# SCH_ECE198-10.net
KiCad netlist of a schematic drawn in EasyEDA
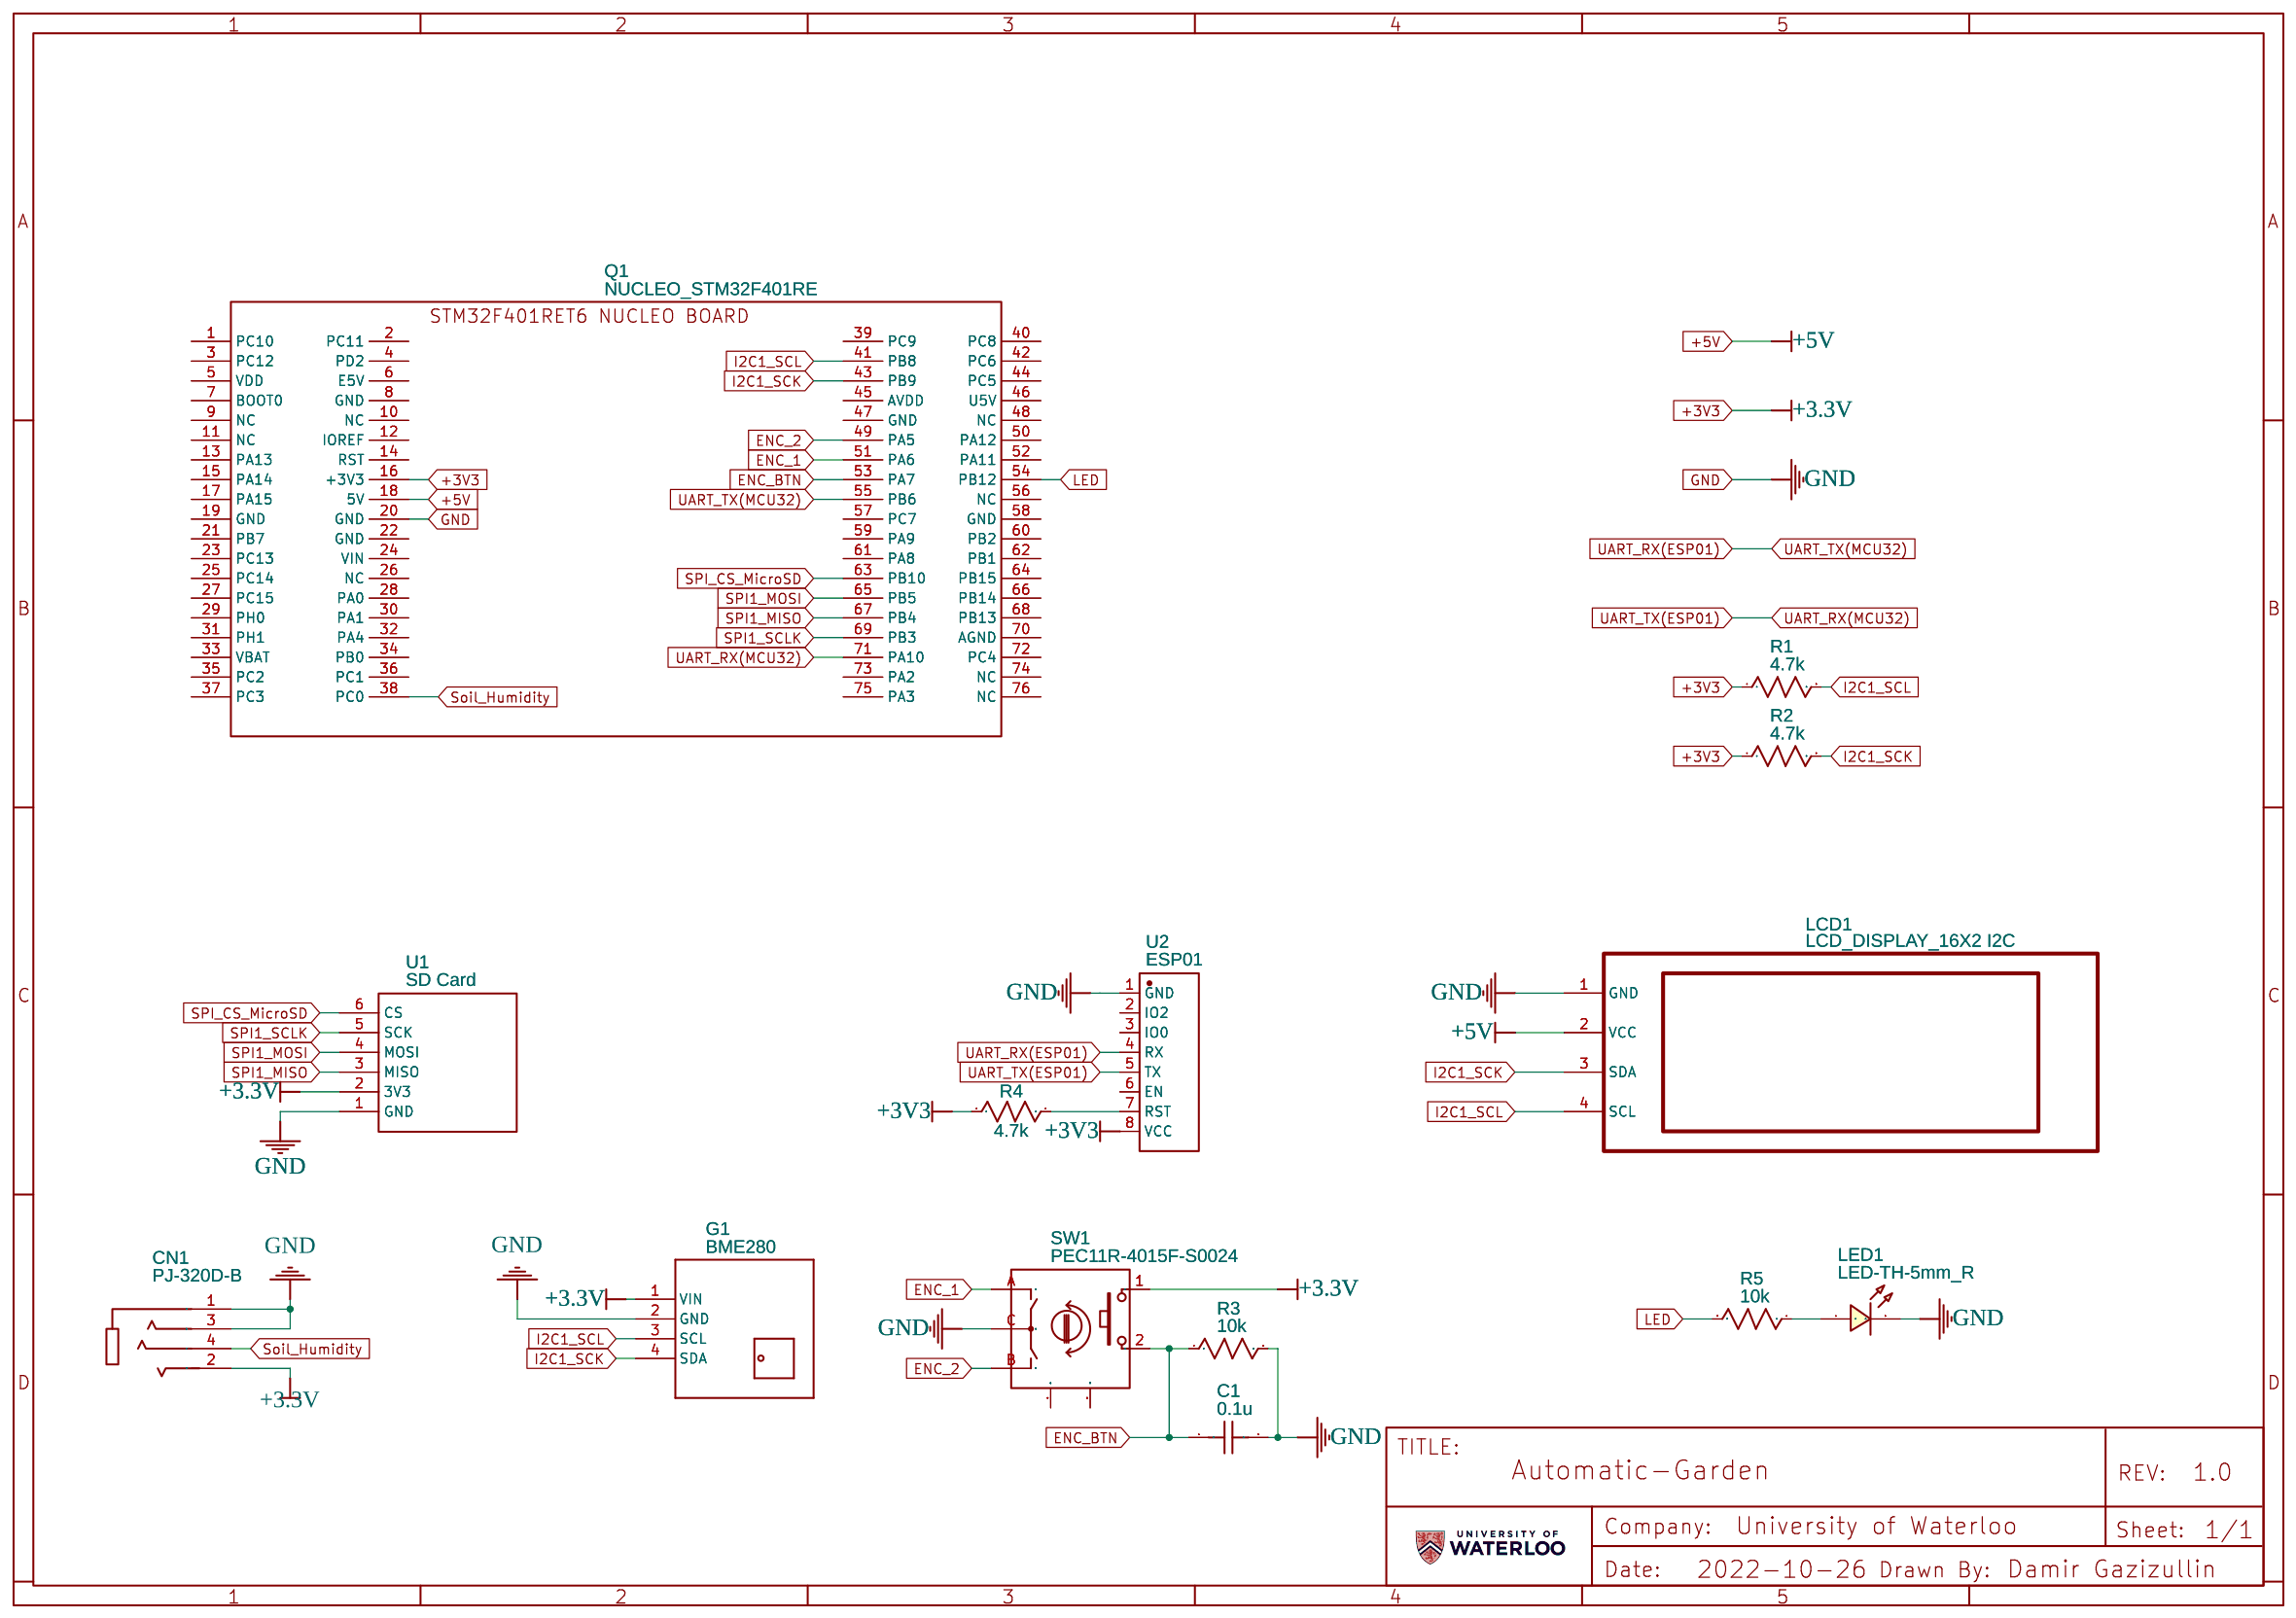
[diagram p0: schematic sheet]

(export (version "E")
  (design (tool "Eeschema 10.0.6"))
  (components
    (comp (ref "C1") (value "0.1u") (libsource (lib "") (part "C_0603_US")))
    (comp (ref "CN1")
      (value "PJ-320D-B")
      (fields (field (name "BOM_Supplier Part") "C2884940"))
      (libsource (lib "") (part "PJ-320D-B"))
    )
    (comp (ref "G1") (value "BME280") (libsource (lib "") (part "TEMP-HUM-PRES-BME280")))
    (comp (ref "LCD1") (value "LCD_DISPLAY_16X2 I2C") (libsource (lib "") (part "LCD_DISPLAY_16X2 I2C")))
    (comp (ref "LED1")
      (value "LED-TH-5mm_R")
      (fields
        (field (name "BOM_Manufacturer Part") "333-2SURD/S530-A3")
        (field (name "BOM_Supplier Part") "C87271")
      )
      (libsource (lib "") (part "LED-TH-5mm_R"))
    )
    (comp (ref "Q1") (value "NUCLEO_STM32F401RE") (libsource (lib "") (part "NUCLEO_STM32F401RE")))
    (comp (ref "R1") (value "4.7k") (libsource (lib "") (part "R_0603_US")))
    (comp (ref "R2") (value "4.7k") (libsource (lib "") (part "R_0603_US")))
    (comp (ref "R3") (value "10k") (libsource (lib "") (part "R_AXIAL-0.5_US")))
    (comp (ref "R4") (value "4.7k") (libsource (lib "") (part "R_AXIAL-0.5_US")))
    (comp (ref "R5") (value "10k") (libsource (lib "") (part "R_AXIAL-0.5_US_1")))
    (comp (ref "SW1")
      (value "PEC11R-4015F-S0024")
      (fields (field (name "BOM_Supplier Part") "C143789"))
      (libsource (lib "") (part "PEC11R-4015F-S0024"))
    )
    (comp (ref "U1") (value "SD Card") (libsource (lib "") (part "SD Card")))
    (comp (ref "U2") (value "ESP01") (libsource (lib "") (part "ESP01")))
  )
  (nets
    (net (code "1") (name "+3V3") (class "Default")
      (node (ref "CN1") (pin "2") (pinfunction "2_2") (pintype "unspecified"))
      (node (ref "G1") (pin "1") (pinfunction "VIN_1") (pintype "bidirectional"))
      (node (ref "Q1") (pin "16") (pinfunction "+3V3_16") (pintype "unspecified"))
      (node (ref "R1") (pin "1") (pinfunction "1_1") (pintype "unspecified"))
      (node (ref "R2") (pin "1") (pinfunction "1_1") (pintype "unspecified"))
      (node (ref "R4") (pin "1") (pinfunction "1_1") (pintype "unspecified"))
      (node (ref "SW1") (pin "1") (pinfunction "1_1") (pintype "unspecified"))
      (node (ref "U1") (pin "2") (pinfunction "3V3_2") (pintype "unspecified"))
      (node (ref "U2") (pin "8") (pinfunction "VCC_8") (pintype "unspecified"))
    )
    (net (code "2") (name "+5V") (class "Default")
      (node (ref "LCD1") (pin "2") (pinfunction "VCC_2") (pintype "passive"))
      (node (ref "Q1") (pin "18") (pinfunction "5V_18") (pintype "unspecified"))
    )
    (net (code "3") (name "ENC_1") (class "Default")
      (node (ref "Q1") (pin "51") (pinfunction "PA6_51") (pintype "unspecified"))
      (node (ref "SW1") (pin "A") (pinfunction "A_A") (pintype "unspecified"))
    )
    (net (code "4") (name "ENC_2") (class "Default")
      (node (ref "Q1") (pin "49") (pinfunction "PA5_49") (pintype "unspecified"))
      (node (ref "SW1") (pin "B") (pinfunction "B_B") (pintype "unspecified"))
    )
    (net (code "5") (name "ENC_BTN") (class "Default")
      (node (ref "C1") (pin "1") (pinfunction "1_1") (pintype "unspecified"))
      (node (ref "Q1") (pin "53") (pinfunction "PA7_53") (pintype "unspecified"))
      (node (ref "R3") (pin "1") (pinfunction "1_1") (pintype "unspecified"))
      (node (ref "SW1") (pin "2") (pinfunction "2_2") (pintype "unspecified"))
    )
    (net (code "6") (name "GND") (class "Default")
      (node (ref "C1") (pin "2") (pinfunction "2_2") (pintype "unspecified"))
      (node (ref "CN1") (pin "1") (pinfunction "1_1") (pintype "unspecified"))
      (node (ref "CN1") (pin "3") (pinfunction "3_3") (pintype "unspecified"))
      (node (ref "G1") (pin "2") (pinfunction "GND_2") (pintype "bidirectional"))
      (node (ref "LCD1") (pin "1") (pinfunction "GND_1") (pintype "passive"))
      (node (ref "LED1") (pin "2") (pinfunction "2_2") (pintype "unspecified"))
      (node (ref "Q1") (pin "20") (pinfunction "GND_20") (pintype "unspecified"))
      (node (ref "R3") (pin "2") (pinfunction "2_2") (pintype "unspecified"))
      (node (ref "SW1") (pin "C") (pinfunction "C_C") (pintype "unspecified"))
      (node (ref "U1") (pin "1") (pinfunction "GND_1") (pintype "unspecified"))
      (node (ref "U2") (pin "1") (pinfunction "GND_1") (pintype "unspecified"))
    )
    (net (code "7") (name "I2C1_SCK") (class "Default")
      (node (ref "G1") (pin "4") (pinfunction "SDA_4") (pintype "bidirectional"))
      (node (ref "LCD1") (pin "3") (pinfunction "SDA_3") (pintype "passive"))
      (node (ref "Q1") (pin "43") (pinfunction "PB9_43") (pintype "unspecified"))
      (node (ref "R2") (pin "2") (pinfunction "2_2") (pintype "unspecified"))
    )
    (net (code "8") (name "I2C1_SCL") (class "Default")
      (node (ref "G1") (pin "3") (pinfunction "SCL_3") (pintype "bidirectional"))
      (node (ref "LCD1") (pin "4") (pinfunction "SCL_4") (pintype "passive"))
      (node (ref "Q1") (pin "41") (pinfunction "PB8_41") (pintype "unspecified"))
      (node (ref "R1") (pin "2") (pinfunction "2_2") (pintype "unspecified"))
    )
    (net (code "9") (name "LED") (class "Default")
      (node (ref "Q1") (pin "54") (pinfunction "PB12_54") (pintype "unspecified"))
      (node (ref "R5") (pin "2") (pinfunction "2_2") (pintype "unspecified"))
    )
    (net (code "10") (name "Net-(LED1-Pad1)") (class "Default")
      (node (ref "LED1") (pin "1") (pinfunction "1_1") (pintype "unspecified"))
      (node (ref "R5") (pin "1") (pinfunction "1_1") (pintype "unspecified"))
    )
    (net (code "11") (name "Net-(U2-RST)") (class "Default")
      (node (ref "R4") (pin "2") (pinfunction "2_2") (pintype "unspecified"))
      (node (ref "U2") (pin "7") (pinfunction "RST_7") (pintype "unspecified"))
    )
    (net (code "12") (name "SPI1_MISO") (class "Default")
      (node (ref "Q1") (pin "67") (pinfunction "PB4_67") (pintype "unspecified"))
      (node (ref "U1") (pin "3") (pinfunction "MISO_3") (pintype "unspecified"))
    )
    (net (code "13") (name "SPI1_MOSI") (class "Default")
      (node (ref "Q1") (pin "65") (pinfunction "PB5_65") (pintype "unspecified"))
      (node (ref "U1") (pin "4") (pinfunction "MOSI_4") (pintype "unspecified"))
    )
    (net (code "14") (name "SPI1_SCLK") (class "Default")
      (node (ref "Q1") (pin "69") (pinfunction "PB3_69") (pintype "unspecified"))
      (node (ref "U1") (pin "5") (pinfunction "SCK_5") (pintype "unspecified"))
    )
    (net (code "15") (name "SPI_CS_MicroSD") (class "Default")
      (node (ref "Q1") (pin "63") (pinfunction "PB10_63") (pintype "unspecified"))
      (node (ref "U1") (pin "6") (pinfunction "CS_6") (pintype "unspecified"))
    )
    (net (code "16") (name "Soil_Humidity") (class "Default")
      (node (ref "CN1") (pin "4") (pinfunction "4_4") (pintype "unspecified"))
      (node (ref "Q1") (pin "38") (pinfunction "PC0_38") (pintype "unspecified"))
    )
    (net (code "17") (name "UART_RX(ESP01)") (class "Default")
      (node (ref "Q1") (pin "55") (pinfunction "PB6_55") (pintype "unspecified"))
      (node (ref "U2") (pin "4") (pinfunction "RX_4") (pintype "unspecified"))
    )
    (net (code "18") (name "UART_RX(MCU32)") (class "Default")
      (node (ref "Q1") (pin "71") (pinfunction "PA10_71") (pintype "unspecified"))
      (node (ref "U2") (pin "5") (pinfunction "TX_5") (pintype "unspecified"))
    )
    (net (code "19") (name "unconnected-(Q1-AGND-Pad70)") (class "Default")
      (node (ref "Q1") (pin "70") (pinfunction "AGND_70") (pintype "unspecified"))
    )
    (net (code "20") (name "unconnected-(Q1-AVDD-Pad45)") (class "Default")
      (node (ref "Q1") (pin "45") (pinfunction "AVDD_45") (pintype "unspecified"))
    )
    (net (code "21") (name "unconnected-(Q1-BOOT0-Pad7)") (class "Default")
      (node (ref "Q1") (pin "7") (pinfunction "BOOT0_7") (pintype "unspecified"))
    )
    (net (code "22") (name "unconnected-(Q1-E5V-Pad6)") (class "Default")
      (node (ref "Q1") (pin "6") (pinfunction "E5V_6") (pintype "unspecified"))
    )
    (net (code "23") (name "unconnected-(Q1-GND-Pad8)") (class "Default")
      (node (ref "Q1") (pin "8") (pinfunction "GND_8") (pintype "unspecified"))
    )
    (net (code "24") (name "unconnected-(Q1-GND-Pad19)") (class "Default")
      (node (ref "Q1") (pin "19") (pinfunction "GND_19") (pintype "unspecified"))
    )
    (net (code "25") (name "unconnected-(Q1-GND-Pad22)") (class "Default")
      (node (ref "Q1") (pin "22") (pinfunction "GND_22") (pintype "unspecified"))
    )
    (net (code "26") (name "unconnected-(Q1-GND-Pad47)") (class "Default")
      (node (ref "Q1") (pin "47") (pinfunction "GND_47") (pintype "unspecified"))
    )
    (net (code "27") (name "unconnected-(Q1-GND-Pad58)") (class "Default")
      (node (ref "Q1") (pin "58") (pinfunction "GND_58") (pintype "unspecified"))
    )
    (net (code "28") (name "unconnected-(Q1-IOREF-Pad12)") (class "Default")
      (node (ref "Q1") (pin "12") (pinfunction "IOREF_12") (pintype "unspecified"))
    )
    (net (code "29") (name "unconnected-(Q1-NC-Pad9)") (class "Default")
      (node (ref "Q1") (pin "9") (pinfunction "NC_9") (pintype "unspecified"))
    )
    (net (code "30") (name "unconnected-(Q1-NC-Pad10)") (class "Default")
      (node (ref "Q1") (pin "10") (pinfunction "NC_10") (pintype "unspecified"))
    )
    (net (code "31") (name "unconnected-(Q1-NC-Pad11)") (class "Default")
      (node (ref "Q1") (pin "11") (pinfunction "NC_11") (pintype "unspecified"))
    )
    (net (code "32") (name "unconnected-(Q1-NC-Pad26)") (class "Default")
      (node (ref "Q1") (pin "26") (pinfunction "NC_26") (pintype "unspecified"))
    )
    (net (code "33") (name "unconnected-(Q1-NC-Pad48)") (class "Default")
      (node (ref "Q1") (pin "48") (pinfunction "NC_48") (pintype "unspecified"))
    )
    (net (code "34") (name "unconnected-(Q1-NC-Pad56)") (class "Default")
      (node (ref "Q1") (pin "56") (pinfunction "NC_56") (pintype "unspecified"))
    )
    (net (code "35") (name "unconnected-(Q1-NC-Pad74)") (class "Default")
      (node (ref "Q1") (pin "74") (pinfunction "NC_74") (pintype "unspecified"))
    )
    (net (code "36") (name "unconnected-(Q1-NC-Pad76)") (class "Default")
      (node (ref "Q1") (pin "76") (pinfunction "NC_76") (pintype "unspecified"))
    )
    (net (code "37") (name "unconnected-(Q1-PA0-Pad28)") (class "Default")
      (node (ref "Q1") (pin "28") (pinfunction "PA0_28") (pintype "unspecified"))
    )
    (net (code "38") (name "unconnected-(Q1-PA1-Pad30)") (class "Default")
      (node (ref "Q1") (pin "30") (pinfunction "PA1_30") (pintype "unspecified"))
    )
    (net (code "39") (name "unconnected-(Q1-PA2-Pad73)") (class "Default")
      (node (ref "Q1") (pin "73") (pinfunction "PA2_73") (pintype "unspecified"))
    )
    (net (code "40") (name "unconnected-(Q1-PA3-Pad75)") (class "Default")
      (node (ref "Q1") (pin "75") (pinfunction "PA3_75") (pintype "unspecified"))
    )
    (net (code "41") (name "unconnected-(Q1-PA4-Pad32)") (class "Default")
      (node (ref "Q1") (pin "32") (pinfunction "PA4_32") (pintype "unspecified"))
    )
    (net (code "42") (name "unconnected-(Q1-PA8-Pad61)") (class "Default")
      (node (ref "Q1") (pin "61") (pinfunction "PA8_61") (pintype "unspecified"))
    )
    (net (code "43") (name "unconnected-(Q1-PA9-Pad59)") (class "Default")
      (node (ref "Q1") (pin "59") (pinfunction "PA9_59") (pintype "unspecified"))
    )
    (net (code "44") (name "unconnected-(Q1-PA11-Pad52)") (class "Default")
      (node (ref "Q1") (pin "52") (pinfunction "PA11_52") (pintype "unspecified"))
    )
    (net (code "45") (name "unconnected-(Q1-PA12-Pad50)") (class "Default")
      (node (ref "Q1") (pin "50") (pinfunction "PA12_50") (pintype "unspecified"))
    )
    (net (code "46") (name "unconnected-(Q1-PA13-Pad13)") (class "Default")
      (node (ref "Q1") (pin "13") (pinfunction "PA13_13") (pintype "unspecified"))
    )
    (net (code "47") (name "unconnected-(Q1-PA14-Pad15)") (class "Default")
      (node (ref "Q1") (pin "15") (pinfunction "PA14_15") (pintype "unspecified"))
    )
    (net (code "48") (name "unconnected-(Q1-PA15-Pad17)") (class "Default")
      (node (ref "Q1") (pin "17") (pinfunction "PA15_17") (pintype "unspecified"))
    )
    (net (code "49") (name "unconnected-(Q1-PB0-Pad34)") (class "Default")
      (node (ref "Q1") (pin "34") (pinfunction "PB0_34") (pintype "unspecified"))
    )
    (net (code "50") (name "unconnected-(Q1-PB1-Pad62)") (class "Default")
      (node (ref "Q1") (pin "62") (pinfunction "PB1_62") (pintype "unspecified"))
    )
    (net (code "51") (name "unconnected-(Q1-PB2-Pad60)") (class "Default")
      (node (ref "Q1") (pin "60") (pinfunction "PB2_60") (pintype "unspecified"))
    )
    (net (code "52") (name "unconnected-(Q1-PB7-Pad21)") (class "Default")
      (node (ref "Q1") (pin "21") (pinfunction "PB7_21") (pintype "unspecified"))
    )
    (net (code "53") (name "unconnected-(Q1-PB13-Pad68)") (class "Default")
      (node (ref "Q1") (pin "68") (pinfunction "PB13_68") (pintype "unspecified"))
    )
    (net (code "54") (name "unconnected-(Q1-PB14-Pad66)") (class "Default")
      (node (ref "Q1") (pin "66") (pinfunction "PB14_66") (pintype "unspecified"))
    )
    (net (code "55") (name "unconnected-(Q1-PB15-Pad64)") (class "Default")
      (node (ref "Q1") (pin "64") (pinfunction "PB15_64") (pintype "unspecified"))
    )
    (net (code "56") (name "unconnected-(Q1-PC1-Pad36)") (class "Default")
      (node (ref "Q1") (pin "36") (pinfunction "PC1_36") (pintype "unspecified"))
    )
    (net (code "57") (name "unconnected-(Q1-PC2-Pad35)") (class "Default")
      (node (ref "Q1") (pin "35") (pinfunction "PC2_35") (pintype "unspecified"))
    )
    (net (code "58") (name "unconnected-(Q1-PC3-Pad37)") (class "Default")
      (node (ref "Q1") (pin "37") (pinfunction "PC3_37") (pintype "unspecified"))
    )
    (net (code "59") (name "unconnected-(Q1-PC4-Pad72)") (class "Default")
      (node (ref "Q1") (pin "72") (pinfunction "PC4_72") (pintype "unspecified"))
    )
    (net (code "60") (name "unconnected-(Q1-PC5-Pad44)") (class "Default")
      (node (ref "Q1") (pin "44") (pinfunction "PC5_44") (pintype "unspecified"))
    )
    (net (code "61") (name "unconnected-(Q1-PC6-Pad42)") (class "Default")
      (node (ref "Q1") (pin "42") (pinfunction "PC6_42") (pintype "unspecified"))
    )
    (net (code "62") (name "unconnected-(Q1-PC7-Pad57)") (class "Default")
      (node (ref "Q1") (pin "57") (pinfunction "PC7_57") (pintype "unspecified"))
    )
    (net (code "63") (name "unconnected-(Q1-PC8-Pad40)") (class "Default")
      (node (ref "Q1") (pin "40") (pinfunction "PC8_40") (pintype "unspecified"))
    )
    (net (code "64") (name "unconnected-(Q1-PC9-Pad39)") (class "Default")
      (node (ref "Q1") (pin "39") (pinfunction "PC9_39") (pintype "unspecified"))
    )
    (net (code "65") (name "unconnected-(Q1-PC10-Pad1)") (class "Default")
      (node (ref "Q1") (pin "1") (pinfunction "PC10_1") (pintype "unspecified"))
    )
    (net (code "66") (name "unconnected-(Q1-PC11-Pad2)") (class "Default")
      (node (ref "Q1") (pin "2") (pinfunction "PC11_2") (pintype "unspecified"))
    )
    (net (code "67") (name "unconnected-(Q1-PC12-Pad3)") (class "Default")
      (node (ref "Q1") (pin "3") (pinfunction "PC12_3") (pintype "unspecified"))
    )
    (net (code "68") (name "unconnected-(Q1-PC13-Pad23)") (class "Default")
      (node (ref "Q1") (pin "23") (pinfunction "PC13_23") (pintype "unspecified"))
    )
    (net (code "69") (name "unconnected-(Q1-PC14-Pad25)") (class "Default")
      (node (ref "Q1") (pin "25") (pinfunction "PC14_25") (pintype "unspecified"))
    )
    (net (code "70") (name "unconnected-(Q1-PC15-Pad27)") (class "Default")
      (node (ref "Q1") (pin "27") (pinfunction "PC15_27") (pintype "unspecified"))
    )
    (net (code "71") (name "unconnected-(Q1-PD2-Pad4)") (class "Default")
      (node (ref "Q1") (pin "4") (pinfunction "PD2_4") (pintype "unspecified"))
    )
    (net (code "72") (name "unconnected-(Q1-PH0-Pad29)") (class "Default")
      (node (ref "Q1") (pin "29") (pinfunction "PH0_29") (pintype "unspecified"))
    )
    (net (code "73") (name "unconnected-(Q1-PH1-Pad31)") (class "Default")
      (node (ref "Q1") (pin "31") (pinfunction "PH1_31") (pintype "unspecified"))
    )
    (net (code "74") (name "unconnected-(Q1-RST-Pad14)") (class "Default")
      (node (ref "Q1") (pin "14") (pinfunction "RST_14") (pintype "unspecified"))
    )
    (net (code "75") (name "unconnected-(Q1-U5V-Pad46)") (class "Default")
      (node (ref "Q1") (pin "46") (pinfunction "U5V_46") (pintype "unspecified"))
    )
    (net (code "76") (name "unconnected-(Q1-VBAT-Pad33)") (class "Default")
      (node (ref "Q1") (pin "33") (pinfunction "VBAT_33") (pintype "unspecified"))
    )
    (net (code "77") (name "unconnected-(Q1-VDD-Pad5)") (class "Default")
      (node (ref "Q1") (pin "5") (pinfunction "VDD_5") (pintype "unspecified"))
    )
    (net (code "78") (name "unconnected-(Q1-VIN-Pad24)") (class "Default")
      (node (ref "Q1") (pin "24") (pinfunction "VIN_24") (pintype "unspecified"))
    )
    (net (code "79") (name "unconnected-(SW1-PadMT1)") (class "Default")
      (node (ref "SW1") (pin "MT1") (pinfunction "MT1_MT1") (pintype "unspecified"))
    )
    (net (code "80") (name "unconnected-(SW1-PadMT2)") (class "Default")
      (node (ref "SW1") (pin "MT2") (pinfunction "MT2_MT2") (pintype "unspecified"))
    )
    (net (code "81") (name "unconnected-(U2-EN-Pad6)") (class "Default")
      (node (ref "U2") (pin "6") (pinfunction "EN_6") (pintype "unspecified"))
    )
    (net (code "82") (name "unconnected-(U2-IO0-Pad3)") (class "Default")
      (node (ref "U2") (pin "3") (pinfunction "IO0_3") (pintype "unspecified"))
    )
    (net (code "83") (name "unconnected-(U2-IO2-Pad2)") (class "Default")
      (node (ref "U2") (pin "2") (pinfunction "IO2_2") (pintype "unspecified"))
    )
  )
)
